# Particle2WeMos.net
KiCad netlist of a schematic drawn in EAGLE
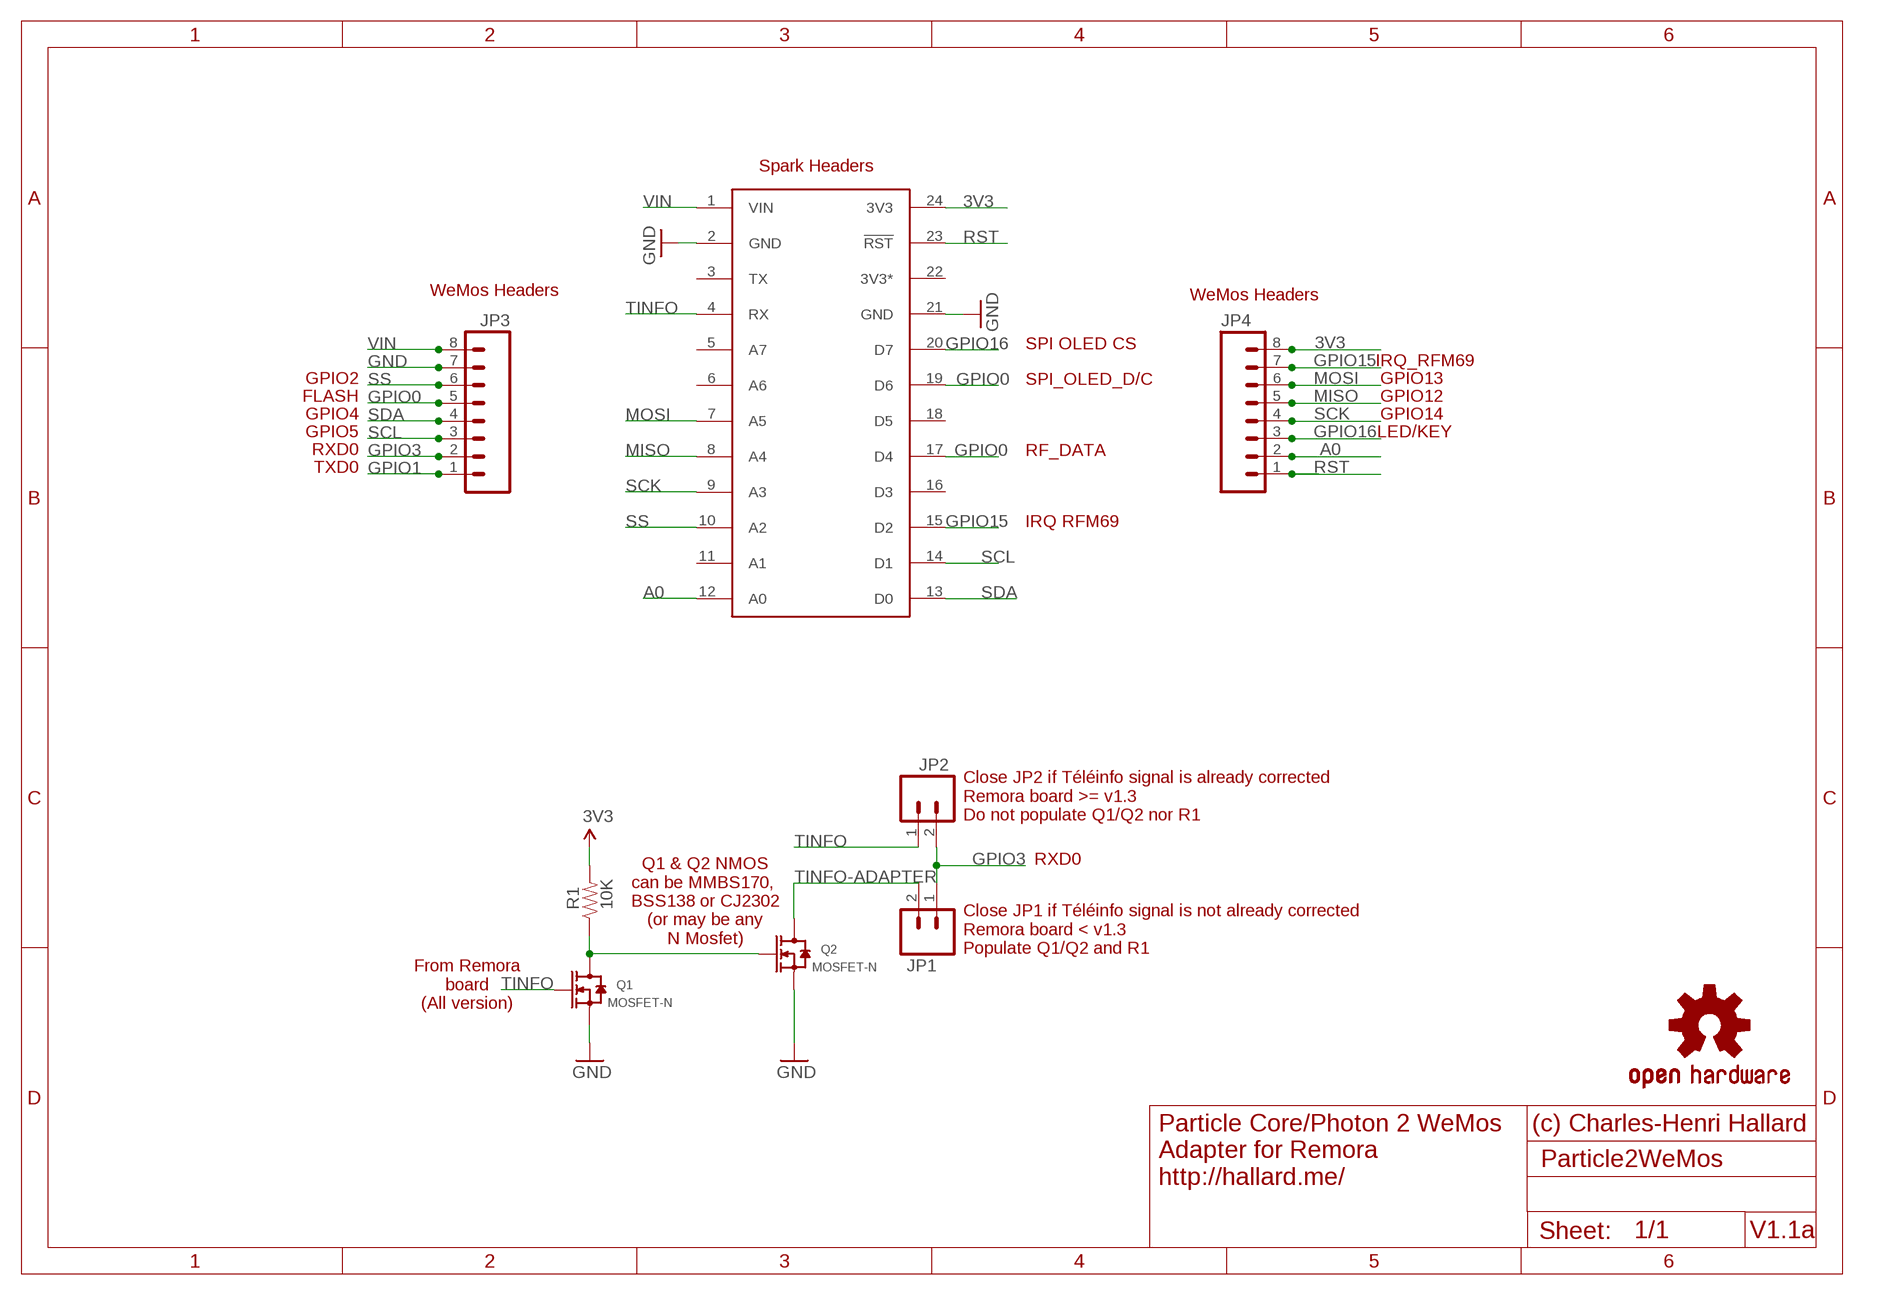
[diagram p0: schematic, sheet 1]

(export (version "E")
  (design (tool "Eeschema 10.0.6"))
  (components
    (comp (ref "JP1")
      (value "M02LOCK")
      (footprint "eagle-import:1X02_LOCK")
      (libsource (lib "eagle-import") (part "M02LOCK"))
    )
    (comp (ref "JP2")
      (value "M02LOCK")
      (footprint "eagle-import:1X02_LOCK")
      (libsource (lib "eagle-import") (part "M02LOCK"))
    )
    (comp (ref "JP3")
      (value "M08SILK_FEMALE_PTH")
      (footprint "eagle-import:1X08")
      (libsource (lib "eagle-import") (part "M08SILK_FEMALE_PTH"))
    )
    (comp (ref "JP4")
      (value "M08SILK_FEMALE_PTH")
      (footprint "eagle-import:1X08")
      (libsource (lib "eagle-import") (part "M08SILK_FEMALE_PTH"))
    )
    (comp (ref "LOGO1")
      (value "OSHW-LOGOM")
      (footprint "eagle-import:OSHW-LOGO-M")
      (libsource (lib "eagle-import") (part "OSHW-LOGOM"))
    )
    (comp (ref "LOGO2")
      (value "OSHW-LOGOM")
      (footprint "eagle-import:OSHW-LOGO-M")
      (libsource (lib "eagle-import") (part "OSHW-LOGOM"))
    )
    (comp (ref "Q1")
      (value "MOSFET-N")
      (footprint "eagle-import:SOT23")
      (libsource (lib "eagle-import") (part "MOSFET-N-''"))
    )
    (comp (ref "Q2")
      (value "MOSFET-N")
      (footprint "eagle-import:SOT23")
      (libsource (lib "eagle-import") (part "MOSFET-N-''"))
    )
    (comp (ref "R1")
      (value "10K")
      (footprint "eagle-import:0805-RES")
      (libsource (lib "eagle-import") (part "RESISTOR0805-RES"))
    )
    (comp (ref "U$2")
      (value "SPARK_CORECORE")
      (footprint "eagle-import:SPARK_CORE")
      (libsource (lib "eagle-import") (part "SPARK_CORECORE"))
    )
  )
  (nets
    (net (code "1") (name "/3V3*") (class "Default")
      (node (ref "U$2") (pin "22") (pinfunction "3V3*_22") (pintype "power_in"))
    )
    (net (code "2") (name "/A0") (class "Default")
      (node (ref "JP4") (pin "2") (pinfunction "2_2") (pintype "passive"))
      (node (ref "U$2") (pin "12") (pinfunction "A0_12") (pintype "bidirectional"))
    )
    (net (code "3") (name "/GPIO0") (class "Default")
      (node (ref "JP3") (pin "5") (pinfunction "5_5") (pintype "passive"))
      (node (ref "U$2") (pin "17") (pinfunction "D4_17") (pintype "bidirectional"))
      (node (ref "U$2") (pin "19") (pinfunction "D6_19") (pintype "bidirectional"))
    )
    (net (code "4") (name "/GPIO1") (class "Default")
      (node (ref "JP3") (pin "1") (pinfunction "1_1") (pintype "passive"))
    )
    (net (code "5") (name "/GPIO3") (class "Default")
      (node (ref "JP1") (pin "1") (pinfunction "1_1") (pintype "passive"))
      (node (ref "JP2") (pin "2") (pinfunction "2_2") (pintype "passive"))
      (node (ref "JP3") (pin "2") (pinfunction "2_2") (pintype "passive"))
    )
    (net (code "6") (name "/GPIO15") (class "Default")
      (node (ref "JP4") (pin "7") (pinfunction "7_7") (pintype "passive"))
      (node (ref "U$2") (pin "15") (pinfunction "D2_15") (pintype "bidirectional"))
    )
    (net (code "7") (name "/GPIO16") (class "Default")
      (node (ref "JP4") (pin "3") (pinfunction "3_3") (pintype "passive"))
      (node (ref "U$2") (pin "20") (pinfunction "D7_20") (pintype "bidirectional"))
    )
    (net (code "8") (name "/MISO") (class "Default")
      (node (ref "JP4") (pin "5") (pinfunction "5_5") (pintype "passive"))
      (node (ref "U$2") (pin "8") (pinfunction "A4_8") (pintype "bidirectional"))
    )
    (net (code "9") (name "/MOSI") (class "Default")
      (node (ref "JP4") (pin "6") (pinfunction "6_6") (pintype "passive"))
      (node (ref "U$2") (pin "7") (pinfunction "A5_7") (pintype "bidirectional"))
    )
    (net (code "10") (name "/RST") (class "Default")
      (node (ref "JP4") (pin "1") (pinfunction "1_1") (pintype "passive"))
      (node (ref "U$2") (pin "23") (pinfunction "~{RST}_23") (pintype "bidirectional"))
    )
    (net (code "11") (name "/SCK") (class "Default")
      (node (ref "JP4") (pin "4") (pinfunction "4_4") (pintype "passive"))
      (node (ref "U$2") (pin "9") (pinfunction "A3_9") (pintype "bidirectional"))
    )
    (net (code "12") (name "/SCL") (class "Default")
      (node (ref "JP3") (pin "3") (pinfunction "3_3") (pintype "passive"))
      (node (ref "U$2") (pin "14") (pinfunction "D1_14") (pintype "bidirectional"))
    )
    (net (code "13") (name "/SDA") (class "Default")
      (node (ref "JP3") (pin "4") (pinfunction "4_4") (pintype "passive"))
      (node (ref "U$2") (pin "13") (pinfunction "D0_13") (pintype "bidirectional"))
    )
    (net (code "14") (name "/SS") (class "Default")
      (node (ref "JP3") (pin "6") (pinfunction "6_6") (pintype "passive"))
      (node (ref "U$2") (pin "10") (pinfunction "A2_10") (pintype "bidirectional"))
    )
    (net (code "15") (name "/TINFO") (class "Default")
      (node (ref "JP2") (pin "1") (pinfunction "1_1") (pintype "passive"))
      (node (ref "Q1") (pin "1") (pinfunction "G_1") (pintype "passive"))
      (node (ref "U$2") (pin "4") (pinfunction "RX_4") (pintype "bidirectional"))
    )
    (net (code "16") (name "/TINFO-ADAPTER") (class "Default")
      (node (ref "JP1") (pin "2") (pinfunction "2_2") (pintype "passive"))
      (node (ref "Q2") (pin "3") (pinfunction "D_3") (pintype "passive"))
    )
    (net (code "17") (name "/VIN") (class "Default")
      (node (ref "JP3") (pin "8") (pinfunction "8_8") (pintype "passive"))
      (node (ref "U$2") (pin "1") (pinfunction "VIN_1") (pintype "power_in"))
    )
    (net (code "18") (name "3V3") (class "Default")
      (node (ref "JP4") (pin "8") (pinfunction "8_8") (pintype "passive"))
      (node (ref "R1") (pin "2") (pinfunction "2_2") (pintype "passive"))
      (node (ref "U$2") (pin "24") (pinfunction "3V3_24") (pintype "power_in"))
    )
    (net (code "19") (name "GND") (class "Default")
      (node (ref "JP3") (pin "7") (pinfunction "7_7") (pintype "passive"))
      (node (ref "Q1") (pin "2") (pinfunction "S_2") (pintype "passive"))
      (node (ref "Q2") (pin "2") (pinfunction "S_2") (pintype "passive"))
      (node (ref "U$2") (pin "2") (pinfunction "GND_2") (pintype "power_in"))
      (node (ref "U$2") (pin "21") (pinfunction "GND_21") (pintype "power_in"))
    )
    (net (code "20") (name "Net-(Q1-D)") (class "Default")
      (node (ref "Q1") (pin "3") (pinfunction "D_3") (pintype "passive"))
      (node (ref "Q2") (pin "1") (pinfunction "G_1") (pintype "passive"))
      (node (ref "R1") (pin "1") (pinfunction "1_1") (pintype "passive"))
    )
    (net (code "21") (name "unconnected-(U$2-A1-Pad11)") (class "Default")
      (node (ref "U$2") (pin "11") (pinfunction "A1_11") (pintype "bidirectional"))
    )
    (net (code "22") (name "unconnected-(U$2-A6-Pad6)") (class "Default")
      (node (ref "U$2") (pin "6") (pinfunction "A6_6") (pintype "bidirectional"))
    )
    (net (code "23") (name "unconnected-(U$2-A7-Pad5)") (class "Default")
      (node (ref "U$2") (pin "5") (pinfunction "A7_5") (pintype "bidirectional"))
    )
    (net (code "24") (name "unconnected-(U$2-D3-Pad16)") (class "Default")
      (node (ref "U$2") (pin "16") (pinfunction "D3_16") (pintype "bidirectional"))
    )
    (net (code "25") (name "unconnected-(U$2-D5-Pad18)") (class "Default")
      (node (ref "U$2") (pin "18") (pinfunction "D5_18") (pintype "bidirectional"))
    )
    (net (code "26") (name "unconnected-(U$2-TX-Pad3)") (class "Default")
      (node (ref "U$2") (pin "3") (pinfunction "TX_3") (pintype "bidirectional"))
    )
  )
)
